# SCH_project-1_2025-10-19.net
KiCad netlist of a schematic drawn in EasyEDA
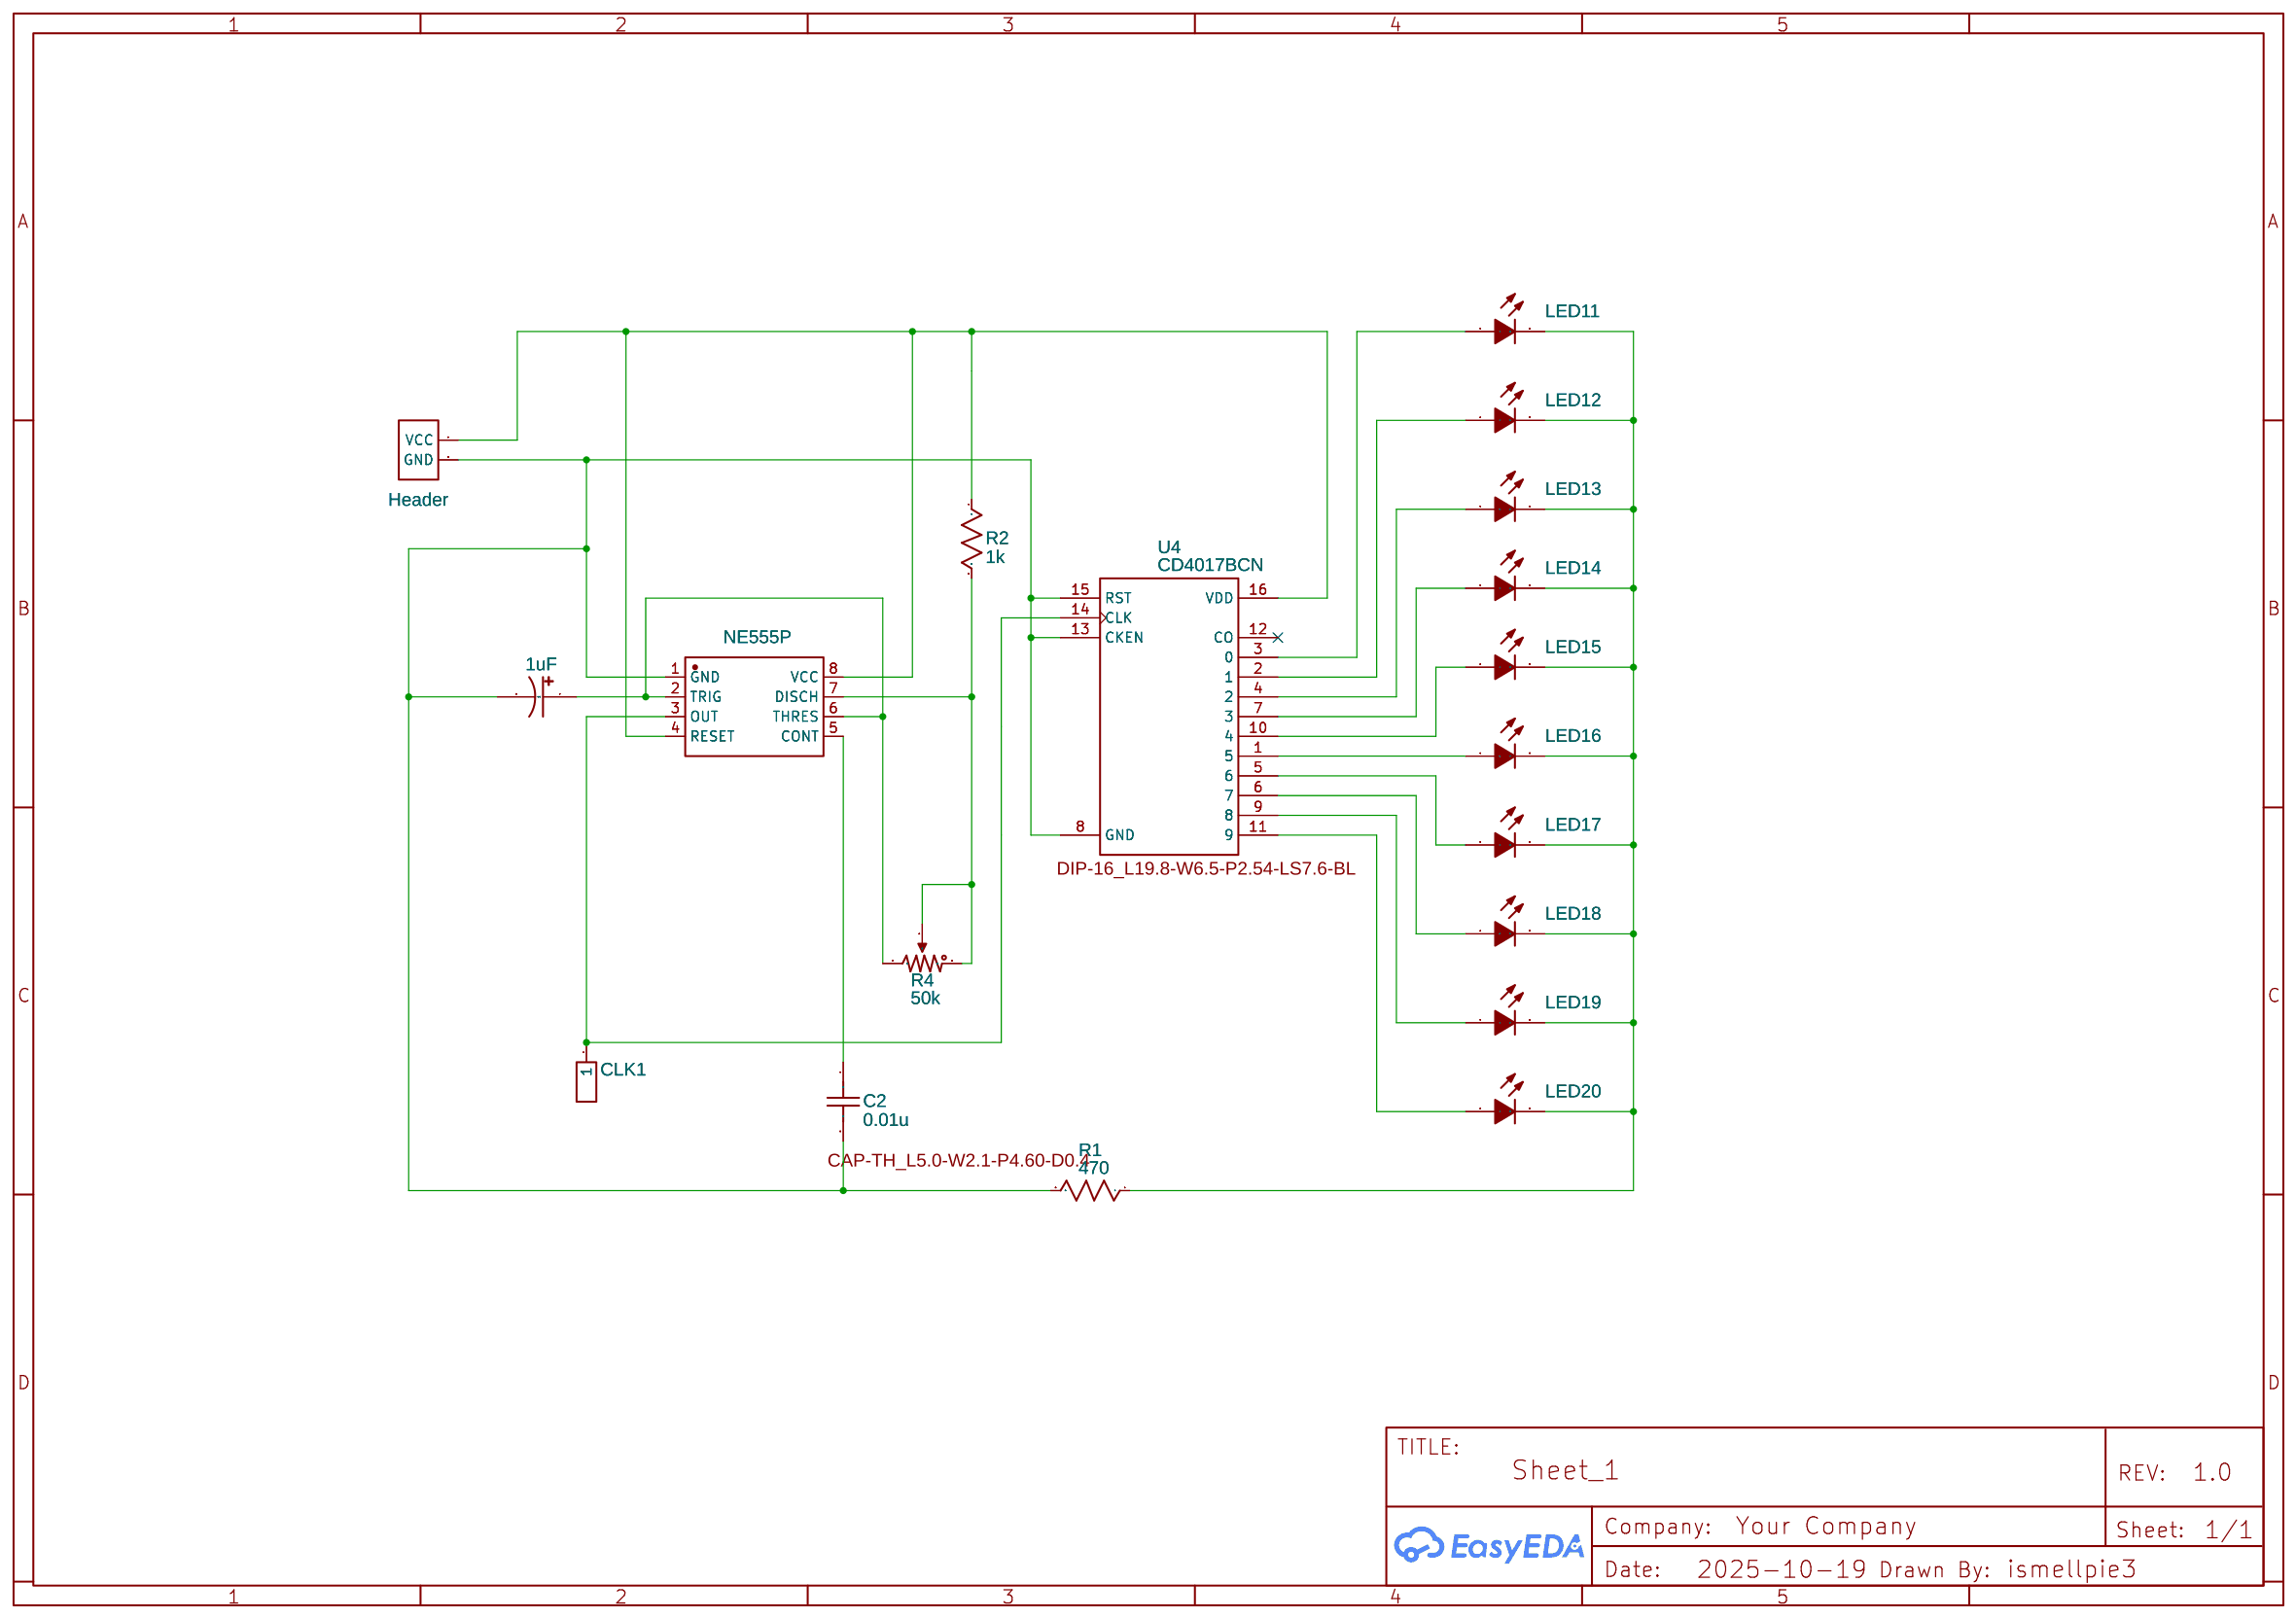
[diagram p0: schematic sheet]

(export (version "E")
  (design (tool "Eeschema 10.0.6"))
  (components
    (comp (ref "C1")
      (value "1uF")
      (fields (field (name "Manufacturer Part") "UVZ1H010MDD") (field (name "Manufacturer") "Nichicon(尼吉康)"))
      (libsource (lib "") (part "UVZ1H010MDD"))
    )
    (comp (ref "C2") (value "0.01u") (libsource (lib "") (part "C_0603_US")))
    (comp (ref "CLK1")
      (value "C81276")
      (fields
        (field (name "Manufacturer Part") "2.54-1*1P针")
        (field (name "Manufacturer") "BOOMELE(Boom Precision Elec)")
      )
      (libsource (lib "") (part "Header-Male-2.54_1x1"))
    )
    (comp (ref "H1") (value "Header") (libsource (lib "") (part "HEADER-FEMALE-2.54_1X2")))
    (comp (ref "LED11") (value "LED_5MM") (libsource (lib "") (part "LED_5MM")))
    (comp (ref "LED12") (value "LED_5MM") (libsource (lib "") (part "LED_5MM")))
    (comp (ref "LED13") (value "LED_5MM") (libsource (lib "") (part "LED_5MM")))
    (comp (ref "LED14") (value "LED_5MM") (libsource (lib "") (part "LED_5MM")))
    (comp (ref "LED15") (value "LED_5MM") (libsource (lib "") (part "LED_5MM")))
    (comp (ref "LED16") (value "LED_5MM") (libsource (lib "") (part "LED_5MM")))
    (comp (ref "LED17") (value "LED_5MM") (libsource (lib "") (part "LED_5MM")))
    (comp (ref "LED18") (value "LED_5MM") (libsource (lib "") (part "LED_5MM")))
    (comp (ref "LED19") (value "LED_5MM") (libsource (lib "") (part "LED_5MM")))
    (comp (ref "LED20") (value "LED_5MM") (libsource (lib "") (part "LED_5MM")))
    (comp (ref "R1")
      (value "470")
      (fields (field (name "Manufacturer Part") "?"))
      (libsource (lib "") (part "Resistor_1"))
    )
    (comp (ref "R2")
      (value "1k")
      (fields (field (name "Manufacturer Part") "?"))
      (libsource (lib "") (part "Resistor"))
    )
    (comp (ref "R4")
      (value "50k")
      (fields (field (name "Manufacturer Part") "?"))
      (libsource (lib "") (part "Potentiometer"))
    )
    (comp (ref "U2")
      (value "NE555P")
      (fields (field (name "Manufacturer") "TI(德州仪器)"))
      (libsource (lib "") (part "NE555P"))
    )
    (comp (ref "U4") (value "CD4017BCN") (libsource (lib "") (part "CD4017BCN")))
  )
  (nets
    (net (code "1") (name "Net-(H1-GND)") (class "Default")
      (node (ref "C1") (pin "2") (pinfunction "2_2") (pintype "unspecified"))
      (node (ref "C2") (pin "2") (pinfunction "2_2") (pintype "unspecified"))
      (node (ref "H1") (pin "2") (pinfunction "GND_2") (pintype "unspecified"))
      (node (ref "R1") (pin "2") (pinfunction "2_2") (pintype "unspecified"))
      (node (ref "U2") (pin "1") (pinfunction "GND_1") (pintype "unspecified"))
      (node (ref "U4") (pin "13") (pinfunction "CKEN_13") (pintype "unspecified"))
      (node (ref "U4") (pin "15") (pinfunction "RST_15") (pintype "unspecified"))
      (node (ref "U4") (pin "8") (pinfunction "GND_8") (pintype "passive"))
    )
    (net (code "2") (name "Net-(H1-VCC)") (class "Default")
      (node (ref "H1") (pin "1") (pinfunction "VCC_1") (pintype "unspecified"))
      (node (ref "R2") (pin "1") (pinfunction "1_1") (pintype "unspecified"))
      (node (ref "U2") (pin "4") (pinfunction "RESET_4") (pintype "unspecified"))
      (node (ref "U2") (pin "8") (pinfunction "VCC_8") (pintype "unspecified"))
      (node (ref "U4") (pin "16") (pinfunction "VDD_16") (pintype "passive"))
    )
    (net (code "3") (name "Net-(LED11-A)") (class "Default")
      (node (ref "LED11") (pin "1") (pinfunction "A_1") (pintype "input"))
      (node (ref "U4") (pin "3") (pinfunction "0_3") (pintype "output"))
    )
    (net (code "4") (name "Net-(LED11-K)") (class "Default")
      (node (ref "LED11") (pin "2") (pinfunction "K_2") (pintype "input"))
      (node (ref "LED12") (pin "2") (pinfunction "K_2") (pintype "input"))
      (node (ref "LED13") (pin "2") (pinfunction "K_2") (pintype "input"))
      (node (ref "LED14") (pin "2") (pinfunction "K_2") (pintype "input"))
      (node (ref "LED15") (pin "2") (pinfunction "K_2") (pintype "input"))
      (node (ref "LED16") (pin "2") (pinfunction "K_2") (pintype "input"))
      (node (ref "LED17") (pin "2") (pinfunction "K_2") (pintype "input"))
      (node (ref "LED18") (pin "2") (pinfunction "K_2") (pintype "input"))
      (node (ref "LED19") (pin "2") (pinfunction "K_2") (pintype "input"))
      (node (ref "LED20") (pin "2") (pinfunction "K_2") (pintype "input"))
      (node (ref "R1") (pin "1") (pinfunction "1_1") (pintype "unspecified"))
    )
    (net (code "5") (name "Net-(LED12-A)") (class "Default")
      (node (ref "LED12") (pin "1") (pinfunction "A_1") (pintype "input"))
      (node (ref "U4") (pin "2") (pinfunction "1_2") (pintype "output"))
    )
    (net (code "6") (name "Net-(LED13-A)") (class "Default")
      (node (ref "LED13") (pin "1") (pinfunction "A_1") (pintype "input"))
      (node (ref "U4") (pin "4") (pinfunction "2_4") (pintype "output"))
    )
    (net (code "7") (name "Net-(LED14-A)") (class "Default")
      (node (ref "LED14") (pin "1") (pinfunction "A_1") (pintype "input"))
      (node (ref "U4") (pin "7") (pinfunction "3_7") (pintype "output"))
    )
    (net (code "8") (name "Net-(LED15-A)") (class "Default")
      (node (ref "LED15") (pin "1") (pinfunction "A_1") (pintype "input"))
      (node (ref "U4") (pin "10") (pinfunction "4_10") (pintype "output"))
    )
    (net (code "9") (name "Net-(LED16-A)") (class "Default")
      (node (ref "LED16") (pin "1") (pinfunction "A_1") (pintype "input"))
      (node (ref "U4") (pin "1") (pinfunction "5_1") (pintype "output"))
    )
    (net (code "10") (name "Net-(LED17-A)") (class "Default")
      (node (ref "LED17") (pin "1") (pinfunction "A_1") (pintype "input"))
      (node (ref "U4") (pin "5") (pinfunction "6_5") (pintype "output"))
    )
    (net (code "11") (name "Net-(LED18-A)") (class "Default")
      (node (ref "LED18") (pin "1") (pinfunction "A_1") (pintype "input"))
      (node (ref "U4") (pin "6") (pinfunction "7_6") (pintype "output"))
    )
    (net (code "12") (name "Net-(LED19-A)") (class "Default")
      (node (ref "LED19") (pin "1") (pinfunction "A_1") (pintype "input"))
      (node (ref "U4") (pin "9") (pinfunction "8_9") (pintype "output"))
    )
    (net (code "13") (name "Net-(LED20-A)") (class "Default")
      (node (ref "LED20") (pin "1") (pinfunction "A_1") (pintype "input"))
      (node (ref "U4") (pin "11") (pinfunction "9_11") (pintype "output"))
    )
    (net (code "14") (name "Net-(R4-2)") (class "Default")
      (node (ref "R2") (pin "2") (pinfunction "2_2") (pintype "unspecified"))
      (node (ref "R4") (pin "2") (pinfunction "3_2") (pintype "unspecified"))
      (node (ref "R4") (pin "3") (pinfunction "2_3") (pintype "unspecified"))
      (node (ref "U2") (pin "7") (pinfunction "DISCH_7") (pintype "unspecified"))
    )
    (net (code "15") (name "Net-(U2-CONT)") (class "Default")
      (node (ref "C2") (pin "1") (pinfunction "1_1") (pintype "unspecified"))
      (node (ref "U2") (pin "5") (pinfunction "CONT_5") (pintype "unspecified"))
    )
    (net (code "16") (name "Net-(U2-OUT)") (class "Default")
      (node (ref "CLK1") (pin "1") (pinfunction "1_1") (pintype "unspecified"))
      (node (ref "U2") (pin "3") (pinfunction "OUT_3") (pintype "unspecified"))
      (node (ref "U4") (pin "14") (pinfunction "CLK_14") (pintype "unspecified"))
    )
    (net (code "17") (name "Net-(U2-THRES)") (class "Default")
      (node (ref "C1") (pin "1") (pinfunction "1_1") (pintype "unspecified"))
      (node (ref "R4") (pin "1") (pinfunction "1_1") (pintype "unspecified"))
      (node (ref "U2") (pin "2") (pinfunction "TRIG_2") (pintype "unspecified"))
      (node (ref "U2") (pin "6") (pinfunction "THRES_6") (pintype "unspecified"))
    )
    (net (code "18") (name "unconnected-(U4-CO-Pad12)") (class "Default")
      (node (ref "U4") (pin "12") (pinfunction "CO_12") (pintype "output+no_connect"))
    )
  )
)
